# 10-M2_GPS.net
KiCad netlist of a schematic drawn in Altium Designer
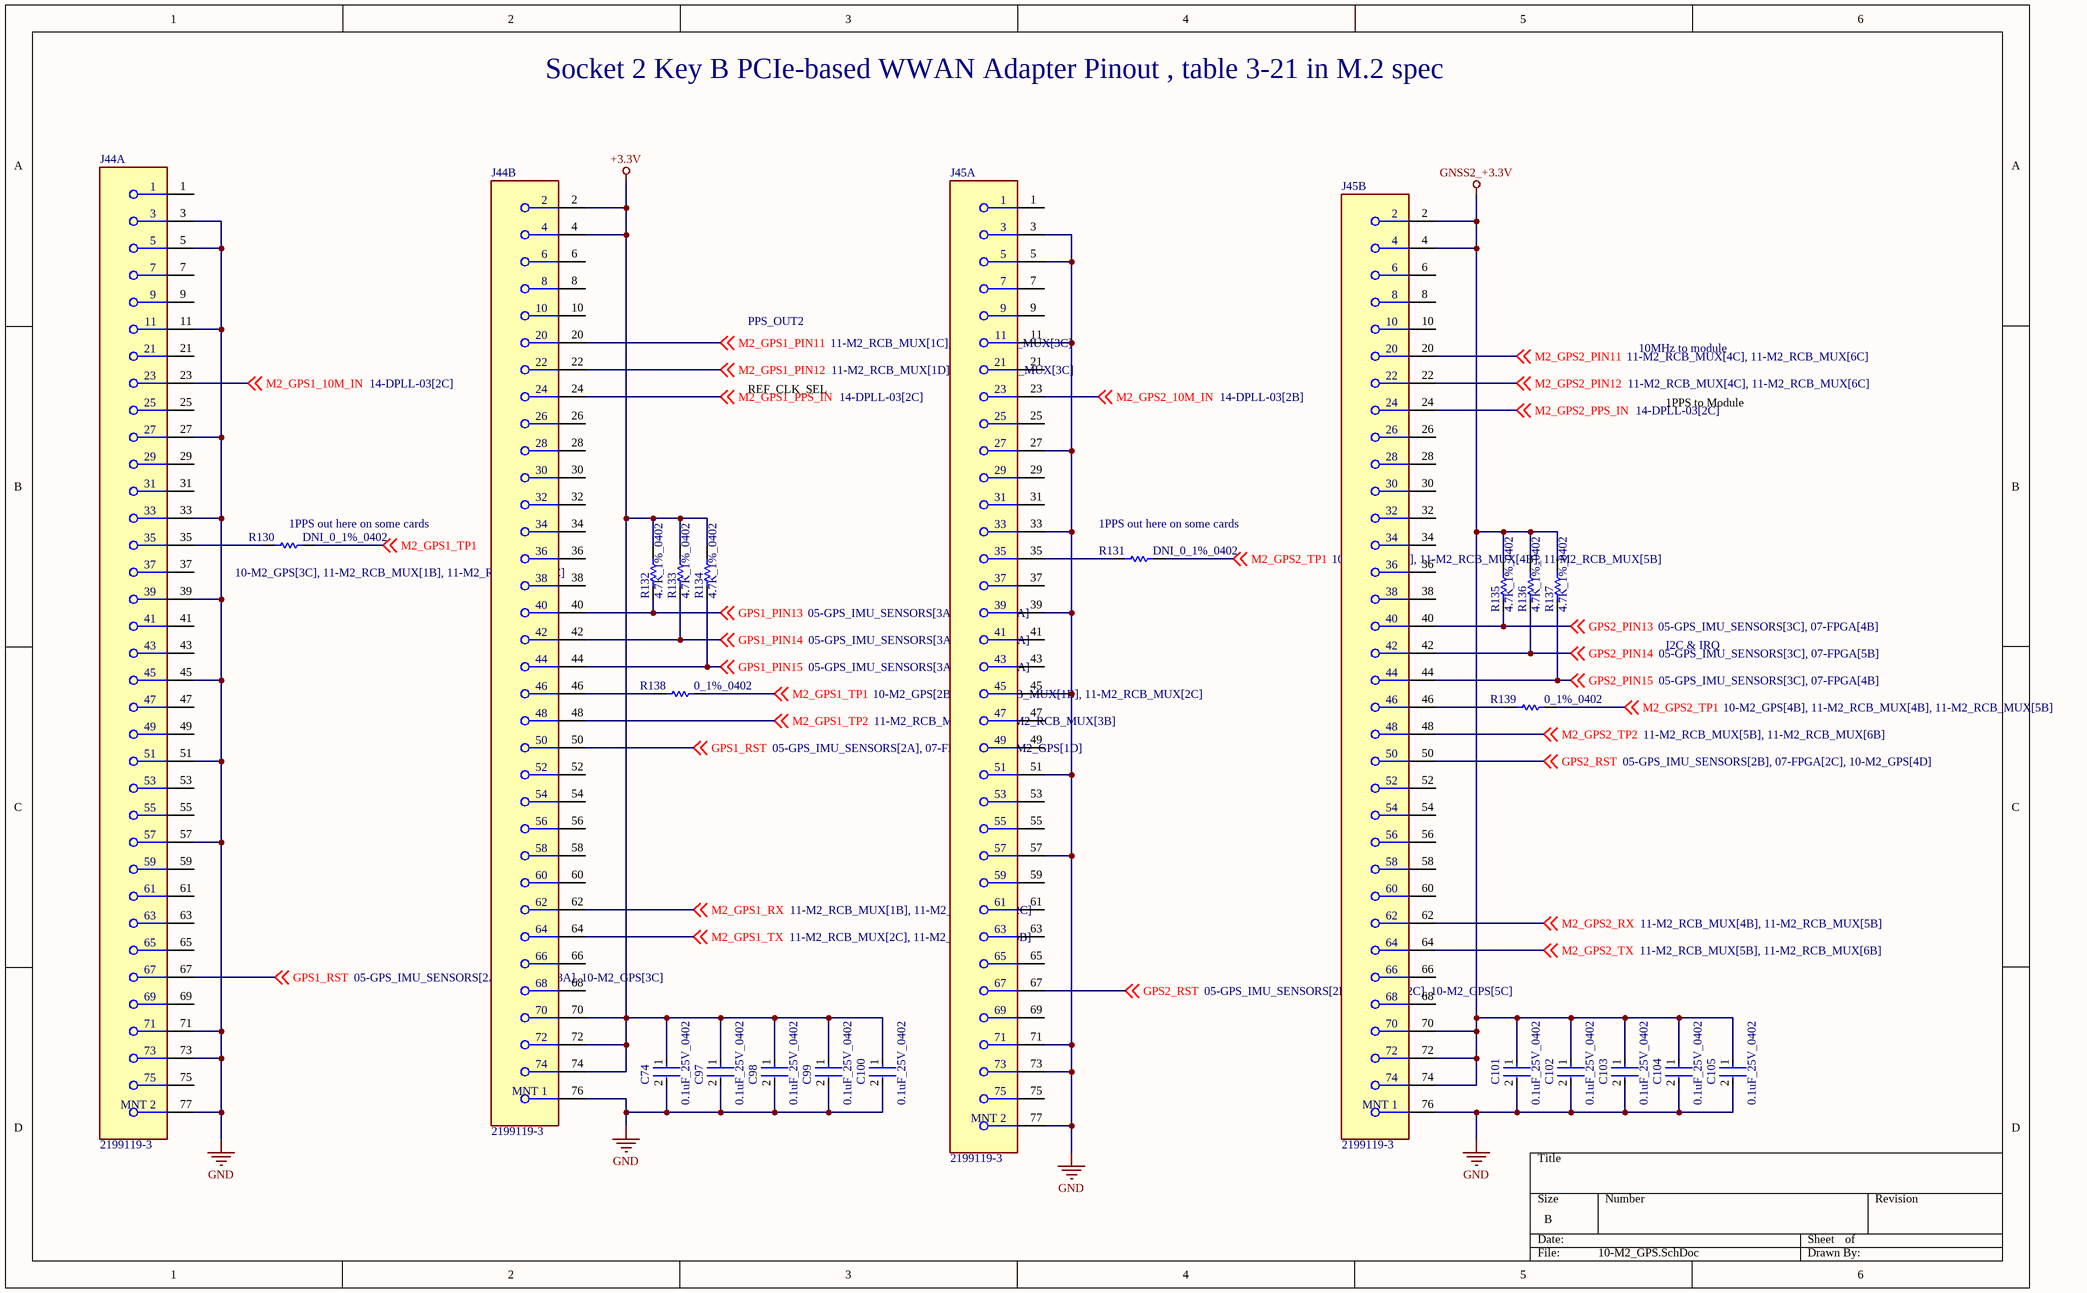
[diagram p0: 10-M2_GPS.SchDoc]

(export (version "E")
  (design (tool "Eeschema 10.0.6"))
  (components
    (comp (ref "C74")
      (value "0.1uF_25V_0402")
      (footprint "FP-0402-L_1_0_1-W_0_5_0_1-IPC_C")
      (description "General Purpose Ceramic Capacitor, 0402, 100nF, 10%, X7R, 15%, 25V")
      (fields (field (name "VOLTAGE") "25V") (field (name "TOLERANCE") "10%"))
      (libsource (lib "Altium Content Vault") (part "b4654b650e69147ec39a6b967a45e02"))
    )
    (comp (ref "C97")
      (value "0.1uF_25V_0402")
      (footprint "FP-0402-L_1_0_1-W_0_5_0_1-IPC_C")
      (description "General Purpose Ceramic Capacitor, 0402, 100nF, 10%, X7R, 15%, 25V")
      (fields (field (name "VOLTAGE") "25V") (field (name "TOLERANCE") "10%"))
      (libsource (lib "Altium Content Vault") (part "b4654b650e69147ec39a6b967a45e02"))
    )
    (comp (ref "C98")
      (value "0.1uF_25V_0402")
      (footprint "FP-0402-L_1_0_1-W_0_5_0_1-IPC_C")
      (description "General Purpose Ceramic Capacitor, 0402, 100nF, 10%, X7R, 15%, 25V")
      (fields (field (name "VOLTAGE") "25V") (field (name "TOLERANCE") "10%"))
      (libsource (lib "Altium Content Vault") (part "b4654b650e69147ec39a6b967a45e02"))
    )
    (comp (ref "C99")
      (value "0.1uF_25V_0402")
      (footprint "FP-0402-L_1_0_1-W_0_5_0_1-IPC_C")
      (description "General Purpose Ceramic Capacitor, 0402, 100nF, 10%, X7R, 15%, 25V")
      (fields (field (name "VOLTAGE") "25V") (field (name "TOLERANCE") "10%"))
      (libsource (lib "Altium Content Vault") (part "b4654b650e69147ec39a6b967a45e02"))
    )
    (comp (ref "C100")
      (value "0.1uF_25V_0402")
      (footprint "FP-0402-L_1_0_1-W_0_5_0_1-IPC_C")
      (description "General Purpose Ceramic Capacitor, 0402, 100nF, 10%, X7R, 15%, 25V")
      (fields (field (name "VOLTAGE") "25V") (field (name "TOLERANCE") "10%"))
      (libsource (lib "Altium Content Vault") (part "b4654b650e69147ec39a6b967a45e02"))
    )
    (comp (ref "C101")
      (value "0.1uF_25V_0402")
      (footprint "FP-0402-L_1_0_1-W_0_5_0_1-IPC_C")
      (description "General Purpose Ceramic Capacitor, 0402, 100nF, 10%, X7R, 15%, 25V")
      (fields (field (name "VOLTAGE") "25V") (field (name "TOLERANCE") "10%"))
      (libsource (lib "Altium Content Vault") (part "b4654b650e69147ec39a6b967a45e02"))
    )
    (comp (ref "C102")
      (value "0.1uF_25V_0402")
      (footprint "FP-0402-L_1_0_1-W_0_5_0_1-IPC_C")
      (description "General Purpose Ceramic Capacitor, 0402, 100nF, 10%, X7R, 15%, 25V")
      (fields (field (name "VOLTAGE") "25V") (field (name "TOLERANCE") "10%"))
      (libsource (lib "Altium Content Vault") (part "b4654b650e69147ec39a6b967a45e02"))
    )
    (comp (ref "C103")
      (value "0.1uF_25V_0402")
      (footprint "FP-0402-L_1_0_1-W_0_5_0_1-IPC_C")
      (description "General Purpose Ceramic Capacitor, 0402, 100nF, 10%, X7R, 15%, 25V")
      (fields (field (name "VOLTAGE") "25V") (field (name "TOLERANCE") "10%"))
      (libsource (lib "Altium Content Vault") (part "b4654b650e69147ec39a6b967a45e02"))
    )
    (comp (ref "C104")
      (value "0.1uF_25V_0402")
      (footprint "FP-0402-L_1_0_1-W_0_5_0_1-IPC_C")
      (description "General Purpose Ceramic Capacitor, 0402, 100nF, 10%, X7R, 15%, 25V")
      (fields (field (name "VOLTAGE") "25V") (field (name "TOLERANCE") "10%"))
      (libsource (lib "Altium Content Vault") (part "b4654b650e69147ec39a6b967a45e02"))
    )
    (comp (ref "C105")
      (value "0.1uF_25V_0402")
      (footprint "FP-0402-L_1_0_1-W_0_5_0_1-IPC_C")
      (description "General Purpose Ceramic Capacitor, 0402, 100nF, 10%, X7R, 15%, 25V")
      (fields (field (name "VOLTAGE") "25V") (field (name "TOLERANCE") "10%"))
      (libsource (lib "Altium Content Vault") (part "b4654b650e69147ec39a6b967a45e02"))
    )
    (comp (ref "J44")
      (value "2199119-3")
      (footprint "FP-2199119-3-MFG")
      (description "CONN M.2 FEMALE 67POS 0.020 GOLD")
      (libsource (lib "Altium Content Vault") (part "a14843ccfa78e5d0b739856168502fb"))
    )
    (comp (ref "J45")
      (value "2199119-3")
      (footprint "FP-2199119-3-MFG")
      (description "CONN M.2 FEMALE 67POS 0.020 GOLD")
      (libsource (lib "Altium Content Vault") (part "a14843ccfa78e5d0b739856168502fb"))
    )
    (comp (ref "R130")
      (value "DNI_0_1%_0402")
      (footprint "RESC1005X40X25LL05T05")
      (description "Chip Resistor, 0 Ohm, 0.1 W, -55 to 155 degC, 0402 (1005 Metric), RoHS, Tape and Reel")
      (fields (field (name "MANUFACTURER") "Panasonic") (field (name "TOLERANCE") "5%"))
      (libsource (lib "Altium Content Vault") (part "RES-2"))
    )
    (comp (ref "R131")
      (value "DNI_0_1%_0402")
      (footprint "RESC1005X40X25LL05T05")
      (description "Chip Resistor, 0 Ohm, 0.1 W, -55 to 155 degC, 0402 (1005 Metric), RoHS, Tape and Reel")
      (fields (field (name "MANUFACTURER") "Panasonic") (field (name "TOLERANCE") "5%"))
      (libsource (lib "Altium Content Vault") (part "RES-2"))
    )
    (comp (ref "R132")
      (value "4.7K_1%_0402")
      (footprint "RESC1005X40X25NL10T10")
      (fields (field (name "MANUFACTURER") "Bourns") (field (name "PART NUMBER") "CR0402-FX-4701GLF"))
      (libsource (lib "Altium Content Vault") (part "RES"))
    )
    (comp (ref "R133")
      (value "4.7K_1%_0402")
      (footprint "RESC1005X40X25NL10T10")
      (fields (field (name "MANUFACTURER") "Bourns") (field (name "PART NUMBER") "CR0402-FX-4701GLF"))
      (libsource (lib "Altium Content Vault") (part "RES"))
    )
    (comp (ref "R134")
      (value "4.7K_1%_0402")
      (footprint "RESC1005X40X25NL10T10")
      (fields (field (name "MANUFACTURER") "Bourns") (field (name "PART NUMBER") "CR0402-FX-4701GLF"))
      (libsource (lib "Altium Content Vault") (part "RES"))
    )
    (comp (ref "R135")
      (value "4.7K_1%_0402")
      (footprint "RESC1005X40X25NL10T10")
      (fields (field (name "MANUFACTURER") "Bourns") (field (name "PART NUMBER") "CR0402-FX-4701GLF"))
      (libsource (lib "Altium Content Vault") (part "RES"))
    )
    (comp (ref "R136")
      (value "4.7K_1%_0402")
      (footprint "RESC1005X40X25NL10T10")
      (fields (field (name "MANUFACTURER") "Bourns") (field (name "PART NUMBER") "CR0402-FX-4701GLF"))
      (libsource (lib "Altium Content Vault") (part "RES"))
    )
    (comp (ref "R137")
      (value "4.7K_1%_0402")
      (footprint "RESC1005X40X25NL10T10")
      (fields (field (name "MANUFACTURER") "Bourns") (field (name "PART NUMBER") "CR0402-FX-4701GLF"))
      (libsource (lib "Altium Content Vault") (part "RES"))
    )
    (comp (ref "R138")
      (value "0_1%_0402")
      (footprint "RESC1005X40X25LL05T05")
      (description "Chip Resistor, 0 Ohm, 0.1 W, -55 to 155 degC, 0402 (1005 Metric), RoHS, Tape and Reel")
      (fields (field (name "MANUFACTURER") "Panasonic") (field (name "TOLERANCE") "5%"))
      (libsource (lib "Altium Content Vault") (part "RES-2"))
    )
    (comp (ref "R139")
      (value "0_1%_0402")
      (footprint "RESC1005X40X25LL05T05")
      (description "Chip Resistor, 0 Ohm, 0.1 W, -55 to 155 degC, 0402 (1005 Metric), RoHS, Tape and Reel")
      (fields (field (name "MANUFACTURER") "Panasonic") (field (name "TOLERANCE") "5%"))
      (libsource (lib "Altium Content Vault") (part "RES-2"))
    )
  )
  (nets
    (net (code "1") (name "+3.3V") (class "Default")
      (node (ref "C100") (pin "1") (pinfunction "1_1") (pintype "passive"))
      (node (ref "C74") (pin "1") (pinfunction "1_1") (pintype "passive"))
      (node (ref "C97") (pin "1") (pinfunction "1_1") (pintype "passive"))
      (node (ref "C98") (pin "1") (pinfunction "1_1") (pintype "passive"))
      (node (ref "C99") (pin "1") (pinfunction "1_1") (pintype "passive"))
      (node (ref "J44") (pin "2") (pinfunction "2_2") (pintype "passive"))
      (node (ref "J44") (pin "4") (pinfunction "4_4") (pintype "passive"))
      (node (ref "J44") (pin "70") (pinfunction "70_70") (pintype "passive"))
      (node (ref "J44") (pin "72") (pinfunction "72_72") (pintype "passive"))
      (node (ref "J44") (pin "74") (pinfunction "74_74") (pintype "passive"))
      (node (ref "R132") (pin "2") (pinfunction "2_2") (pintype "passive"))
      (node (ref "R133") (pin "2") (pinfunction "2_2") (pintype "passive"))
      (node (ref "R134") (pin "2") (pinfunction "2_2") (pintype "passive"))
    )
    (net (code "2") (name "GND") (class "Default")
      (node (ref "C100") (pin "2") (pinfunction "2_2") (pintype "passive"))
      (node (ref "C101") (pin "2") (pinfunction "2_2") (pintype "passive"))
      (node (ref "C102") (pin "2") (pinfunction "2_2") (pintype "passive"))
      (node (ref "C103") (pin "2") (pinfunction "2_2") (pintype "passive"))
      (node (ref "C104") (pin "2") (pinfunction "2_2") (pintype "passive"))
      (node (ref "C105") (pin "2") (pinfunction "2_2") (pintype "passive"))
      (node (ref "C74") (pin "2") (pinfunction "2_2") (pintype "passive"))
      (node (ref "C97") (pin "2") (pinfunction "2_2") (pintype "passive"))
      (node (ref "C98") (pin "2") (pinfunction "2_2") (pintype "passive"))
      (node (ref "C99") (pin "2") (pinfunction "2_2") (pintype "passive"))
      (node (ref "J44") (pin "11") (pinfunction "11_11") (pintype "passive"))
      (node (ref "J44") (pin "27") (pinfunction "27_27") (pintype "passive"))
      (node (ref "J44") (pin "3") (pinfunction "3_3") (pintype "passive"))
      (node (ref "J44") (pin "33") (pinfunction "33_33") (pintype "passive"))
      (node (ref "J44") (pin "39") (pinfunction "39_39") (pintype "passive"))
      (node (ref "J44") (pin "45") (pinfunction "45_45") (pintype "passive"))
      (node (ref "J44") (pin "5") (pinfunction "5_5") (pintype "passive"))
      (node (ref "J44") (pin "51") (pinfunction "51_51") (pintype "passive"))
      (node (ref "J44") (pin "57") (pinfunction "57_57") (pintype "passive"))
      (node (ref "J44") (pin "71") (pinfunction "71_71") (pintype "passive"))
      (node (ref "J44") (pin "73") (pinfunction "73_73") (pintype "passive"))
      (node (ref "J44") (pin "76") (pinfunction "MNT_1_76") (pintype "passive"))
      (node (ref "J44") (pin "77") (pinfunction "MNT_2_77") (pintype "passive"))
      (node (ref "J45") (pin "11") (pinfunction "11_11") (pintype "passive"))
      (node (ref "J45") (pin "27") (pinfunction "27_27") (pintype "passive"))
      (node (ref "J45") (pin "3") (pinfunction "3_3") (pintype "passive"))
      (node (ref "J45") (pin "33") (pinfunction "33_33") (pintype "passive"))
      (node (ref "J45") (pin "39") (pinfunction "39_39") (pintype "passive"))
      (node (ref "J45") (pin "45") (pinfunction "45_45") (pintype "passive"))
      (node (ref "J45") (pin "5") (pinfunction "5_5") (pintype "passive"))
      (node (ref "J45") (pin "51") (pinfunction "51_51") (pintype "passive"))
      (node (ref "J45") (pin "57") (pinfunction "57_57") (pintype "passive"))
      (node (ref "J45") (pin "71") (pinfunction "71_71") (pintype "passive"))
      (node (ref "J45") (pin "73") (pinfunction "73_73") (pintype "passive"))
      (node (ref "J45") (pin "76") (pinfunction "MNT_1_76") (pintype "passive"))
      (node (ref "J45") (pin "77") (pinfunction "MNT_2_77") (pintype "passive"))
    )
    (net (code "3") (name "GNSS2_+3.3V") (class "Default")
      (node (ref "C101") (pin "1") (pinfunction "1_1") (pintype "passive"))
      (node (ref "C102") (pin "1") (pinfunction "1_1") (pintype "passive"))
      (node (ref "C103") (pin "1") (pinfunction "1_1") (pintype "passive"))
      (node (ref "C104") (pin "1") (pinfunction "1_1") (pintype "passive"))
      (node (ref "C105") (pin "1") (pinfunction "1_1") (pintype "passive"))
      (node (ref "J45") (pin "2") (pinfunction "2_2") (pintype "passive"))
      (node (ref "J45") (pin "4") (pinfunction "4_4") (pintype "passive"))
      (node (ref "J45") (pin "70") (pinfunction "70_70") (pintype "passive"))
      (node (ref "J45") (pin "72") (pinfunction "72_72") (pintype "passive"))
      (node (ref "J45") (pin "74") (pinfunction "74_74") (pintype "passive"))
      (node (ref "R135") (pin "2") (pinfunction "2_2") (pintype "passive"))
      (node (ref "R136") (pin "2") (pinfunction "2_2") (pintype "passive"))
      (node (ref "R137") (pin "2") (pinfunction "2_2") (pintype "passive"))
    )
    (net (code "4") (name "GPS1_PIN13") (class "Default")
      (node (ref "J44") (pin "40") (pinfunction "40_40") (pintype "passive"))
      (node (ref "R132") (pin "1") (pinfunction "1_1") (pintype "passive"))
    )
    (net (code "5") (name "GPS1_PIN14") (class "Default")
      (node (ref "J44") (pin "42") (pinfunction "42_42") (pintype "passive"))
      (node (ref "R133") (pin "1") (pinfunction "1_1") (pintype "passive"))
    )
    (net (code "6") (name "GPS1_PIN15") (class "Default")
      (node (ref "J44") (pin "44") (pinfunction "44_44") (pintype "passive"))
      (node (ref "R134") (pin "1") (pinfunction "1_1") (pintype "passive"))
    )
    (net (code "7") (name "GPS1_RST") (class "Default")
      (node (ref "J44") (pin "50") (pinfunction "50_50") (pintype "passive"))
      (node (ref "J44") (pin "67") (pinfunction "67_67") (pintype "passive"))
    )
    (net (code "8") (name "GPS2_PIN13") (class "Default")
      (node (ref "J45") (pin "40") (pinfunction "40_40") (pintype "passive"))
      (node (ref "R135") (pin "1") (pinfunction "1_1") (pintype "passive"))
    )
    (net (code "9") (name "GPS2_PIN14") (class "Default")
      (node (ref "J45") (pin "42") (pinfunction "42_42") (pintype "passive"))
      (node (ref "R136") (pin "1") (pinfunction "1_1") (pintype "passive"))
    )
    (net (code "10") (name "GPS2_PIN15") (class "Default")
      (node (ref "J45") (pin "44") (pinfunction "44_44") (pintype "passive"))
      (node (ref "R137") (pin "1") (pinfunction "1_1") (pintype "passive"))
    )
    (net (code "11") (name "GPS2_RST") (class "Default")
      (node (ref "J45") (pin "50") (pinfunction "50_50") (pintype "passive"))
      (node (ref "J45") (pin "67") (pinfunction "67_67") (pintype "passive"))
    )
    (net (code "12") (name "M2_GPS1_10M_IN") (class "Default")
      (node (ref "J44") (pin "23") (pinfunction "23_23") (pintype "passive"))
    )
    (net (code "13") (name "M2_GPS1_PIN11") (class "Default")
      (node (ref "J44") (pin "20") (pinfunction "20_20") (pintype "passive"))
    )
    (net (code "14") (name "M2_GPS1_PIN12") (class "Default")
      (node (ref "J44") (pin "22") (pinfunction "22_22") (pintype "passive"))
    )
    (net (code "15") (name "M2_GPS1_PPS_IN") (class "Default")
      (node (ref "J44") (pin "24") (pinfunction "24_24") (pintype "passive"))
    )
    (net (code "16") (name "M2_GPS1_RX") (class "Default")
      (node (ref "J44") (pin "62") (pinfunction "62_62") (pintype "passive"))
    )
    (net (code "17") (name "M2_GPS1_TP1") (class "Default")
      (node (ref "R130") (pin "2") (pinfunction "2_2") (pintype "passive"))
      (node (ref "R138") (pin "2") (pinfunction "2_2") (pintype "passive"))
    )
    (net (code "18") (name "M2_GPS1_TP2") (class "Default")
      (node (ref "J44") (pin "48") (pinfunction "48_48") (pintype "passive"))
    )
    (net (code "19") (name "M2_GPS1_TX") (class "Default")
      (node (ref "J44") (pin "64") (pinfunction "64_64") (pintype "passive"))
    )
    (net (code "20") (name "M2_GPS2_10M_IN") (class "Default")
      (node (ref "J45") (pin "23") (pinfunction "23_23") (pintype "passive"))
    )
    (net (code "21") (name "M2_GPS2_PIN11") (class "Default")
      (node (ref "J45") (pin "20") (pinfunction "20_20") (pintype "passive"))
    )
    (net (code "22") (name "M2_GPS2_PIN12") (class "Default")
      (node (ref "J45") (pin "22") (pinfunction "22_22") (pintype "passive"))
    )
    (net (code "23") (name "M2_GPS2_PPS_IN") (class "Default")
      (node (ref "J45") (pin "24") (pinfunction "24_24") (pintype "passive"))
    )
    (net (code "24") (name "M2_GPS2_RX") (class "Default")
      (node (ref "J45") (pin "62") (pinfunction "62_62") (pintype "passive"))
    )
    (net (code "25") (name "M2_GPS2_TP1") (class "Default")
      (node (ref "R131") (pin "2") (pinfunction "2_2") (pintype "passive"))
      (node (ref "R139") (pin "2") (pinfunction "2_2") (pintype "passive"))
    )
    (net (code "26") (name "M2_GPS2_TP2") (class "Default")
      (node (ref "J45") (pin "48") (pinfunction "48_48") (pintype "passive"))
    )
    (net (code "27") (name "M2_GPS2_TX") (class "Default")
      (node (ref "J45") (pin "64") (pinfunction "64_64") (pintype "passive"))
    )
    (net (code "28") (name "Net-(J44-Pad35)") (class "Default")
      (node (ref "J44") (pin "35") (pinfunction "35_35") (pintype "passive"))
      (node (ref "R130") (pin "1") (pinfunction "1_1") (pintype "passive"))
    )
    (net (code "29") (name "Net-(J44-Pad46)") (class "Default")
      (node (ref "J44") (pin "46") (pinfunction "46_46") (pintype "passive"))
      (node (ref "R138") (pin "1") (pinfunction "1_1") (pintype "passive"))
    )
    (net (code "30") (name "Net-(J45-Pad35)") (class "Default")
      (node (ref "J45") (pin "35") (pinfunction "35_35") (pintype "passive"))
      (node (ref "R131") (pin "1") (pinfunction "1_1") (pintype "passive"))
    )
    (net (code "31") (name "Net-(J45-Pad46)") (class "Default")
      (node (ref "J45") (pin "46") (pinfunction "46_46") (pintype "passive"))
      (node (ref "R139") (pin "1") (pinfunction "1_1") (pintype "passive"))
    )
    (net (code "32") (name "unconnected-(J44-Pad1)") (class "Default")
      (node (ref "J44") (pin "1") (pinfunction "1_1") (pintype "passive"))
    )
    (net (code "33") (name "unconnected-(J44-Pad6)") (class "Default")
      (node (ref "J44") (pin "6") (pinfunction "6_6") (pintype "passive"))
    )
    (net (code "34") (name "unconnected-(J44-Pad7)") (class "Default")
      (node (ref "J44") (pin "7") (pinfunction "7_7") (pintype "passive"))
    )
    (net (code "35") (name "unconnected-(J44-Pad8)") (class "Default")
      (node (ref "J44") (pin "8") (pinfunction "8_8") (pintype "passive"))
    )
    (net (code "36") (name "unconnected-(J44-Pad9)") (class "Default")
      (node (ref "J44") (pin "9") (pinfunction "9_9") (pintype "passive"))
    )
    (net (code "37") (name "unconnected-(J44-Pad10)") (class "Default")
      (node (ref "J44") (pin "10") (pinfunction "10_10") (pintype "passive"))
    )
    (net (code "38") (name "unconnected-(J44-Pad21)") (class "Default")
      (node (ref "J44") (pin "21") (pinfunction "21_21") (pintype "passive"))
    )
    (net (code "39") (name "unconnected-(J44-Pad25)") (class "Default")
      (node (ref "J44") (pin "25") (pinfunction "25_25") (pintype "passive"))
    )
    (net (code "40") (name "unconnected-(J44-Pad26)") (class "Default")
      (node (ref "J44") (pin "26") (pinfunction "26_26") (pintype "passive"))
    )
    (net (code "41") (name "unconnected-(J44-Pad28)") (class "Default")
      (node (ref "J44") (pin "28") (pinfunction "28_28") (pintype "passive"))
    )
    (net (code "42") (name "unconnected-(J44-Pad29)") (class "Default")
      (node (ref "J44") (pin "29") (pinfunction "29_29") (pintype "passive"))
    )
    (net (code "43") (name "unconnected-(J44-Pad30)") (class "Default")
      (node (ref "J44") (pin "30") (pinfunction "30_30") (pintype "passive"))
    )
    (net (code "44") (name "unconnected-(J44-Pad31)") (class "Default")
      (node (ref "J44") (pin "31") (pinfunction "31_31") (pintype "passive"))
    )
    (net (code "45") (name "unconnected-(J44-Pad32)") (class "Default")
      (node (ref "J44") (pin "32") (pinfunction "32_32") (pintype "passive"))
    )
    (net (code "46") (name "unconnected-(J44-Pad34)") (class "Default")
      (node (ref "J44") (pin "34") (pinfunction "34_34") (pintype "passive"))
    )
    (net (code "47") (name "unconnected-(J44-Pad36)") (class "Default")
      (node (ref "J44") (pin "36") (pinfunction "36_36") (pintype "passive"))
    )
    (net (code "48") (name "unconnected-(J44-Pad37)") (class "Default")
      (node (ref "J44") (pin "37") (pinfunction "37_37") (pintype "passive"))
    )
    (net (code "49") (name "unconnected-(J44-Pad38)") (class "Default")
      (node (ref "J44") (pin "38") (pinfunction "38_38") (pintype "passive"))
    )
    (net (code "50") (name "unconnected-(J44-Pad41)") (class "Default")
      (node (ref "J44") (pin "41") (pinfunction "41_41") (pintype "passive"))
    )
    (net (code "51") (name "unconnected-(J44-Pad43)") (class "Default")
      (node (ref "J44") (pin "43") (pinfunction "43_43") (pintype "passive"))
    )
    (net (code "52") (name "unconnected-(J44-Pad47)") (class "Default")
      (node (ref "J44") (pin "47") (pinfunction "47_47") (pintype "passive"))
    )
    (net (code "53") (name "unconnected-(J44-Pad49)") (class "Default")
      (node (ref "J44") (pin "49") (pinfunction "49_49") (pintype "passive"))
    )
    (net (code "54") (name "unconnected-(J44-Pad52)") (class "Default")
      (node (ref "J44") (pin "52") (pinfunction "52_52") (pintype "passive"))
    )
    (net (code "55") (name "unconnected-(J44-Pad53)") (class "Default")
      (node (ref "J44") (pin "53") (pinfunction "53_53") (pintype "passive"))
    )
    (net (code "56") (name "unconnected-(J44-Pad54)") (class "Default")
      (node (ref "J44") (pin "54") (pinfunction "54_54") (pintype "passive"))
    )
    (net (code "57") (name "unconnected-(J44-Pad55)") (class "Default")
      (node (ref "J44") (pin "55") (pinfunction "55_55") (pintype "passive"))
    )
    (net (code "58") (name "unconnected-(J44-Pad56)") (class "Default")
      (node (ref "J44") (pin "56") (pinfunction "56_56") (pintype "passive"))
    )
    (net (code "59") (name "unconnected-(J44-Pad58)") (class "Default")
      (node (ref "J44") (pin "58") (pinfunction "58_58") (pintype "passive"))
    )
    (net (code "60") (name "unconnected-(J44-Pad59)") (class "Default")
      (node (ref "J44") (pin "59") (pinfunction "59_59") (pintype "passive"))
    )
    (net (code "61") (name "unconnected-(J44-Pad60)") (class "Default")
      (node (ref "J44") (pin "60") (pinfunction "60_60") (pintype "passive"))
    )
    (net (code "62") (name "unconnected-(J44-Pad61)") (class "Default")
      (node (ref "J44") (pin "61") (pinfunction "61_61") (pintype "passive"))
    )
    (net (code "63") (name "unconnected-(J44-Pad63)") (class "Default")
      (node (ref "J44") (pin "63") (pinfunction "63_63") (pintype "passive"))
    )
    (net (code "64") (name "unconnected-(J44-Pad65)") (class "Default")
      (node (ref "J44") (pin "65") (pinfunction "65_65") (pintype "passive"))
    )
    (net (code "65") (name "unconnected-(J44-Pad66)") (class "Default")
      (node (ref "J44") (pin "66") (pinfunction "66_66") (pintype "passive"))
    )
    (net (code "66") (name "unconnected-(J44-Pad68)") (class "Default")
      (node (ref "J44") (pin "68") (pinfunction "68_68") (pintype "passive"))
    )
    (net (code "67") (name "unconnected-(J44-Pad69)") (class "Default")
      (node (ref "J44") (pin "69") (pinfunction "69_69") (pintype "passive"))
    )
    (net (code "68") (name "unconnected-(J44-Pad75)") (class "Default")
      (node (ref "J44") (pin "75") (pinfunction "75_75") (pintype "passive"))
    )
    (net (code "69") (name "unconnected-(J45-Pad1)") (class "Default")
      (node (ref "J45") (pin "1") (pinfunction "1_1") (pintype "passive"))
    )
    (net (code "70") (name "unconnected-(J45-Pad6)") (class "Default")
      (node (ref "J45") (pin "6") (pinfunction "6_6") (pintype "passive"))
    )
    (net (code "71") (name "unconnected-(J45-Pad7)") (class "Default")
      (node (ref "J45") (pin "7") (pinfunction "7_7") (pintype "passive"))
    )
    (net (code "72") (name "unconnected-(J45-Pad8)") (class "Default")
      (node (ref "J45") (pin "8") (pinfunction "8_8") (pintype "passive"))
    )
    (net (code "73") (name "unconnected-(J45-Pad9)") (class "Default")
      (node (ref "J45") (pin "9") (pinfunction "9_9") (pintype "passive"))
    )
    (net (code "74") (name "unconnected-(J45-Pad10)") (class "Default")
      (node (ref "J45") (pin "10") (pinfunction "10_10") (pintype "passive"))
    )
    (net (code "75") (name "unconnected-(J45-Pad21)") (class "Default")
      (node (ref "J45") (pin "21") (pinfunction "21_21") (pintype "passive"))
    )
    (net (code "76") (name "unconnected-(J45-Pad25)") (class "Default")
      (node (ref "J45") (pin "25") (pinfunction "25_25") (pintype "passive"))
    )
    (net (code "77") (name "unconnected-(J45-Pad26)") (class "Default")
      (node (ref "J45") (pin "26") (pinfunction "26_26") (pintype "passive"))
    )
    (net (code "78") (name "unconnected-(J45-Pad28)") (class "Default")
      (node (ref "J45") (pin "28") (pinfunction "28_28") (pintype "passive"))
    )
    (net (code "79") (name "unconnected-(J45-Pad29)") (class "Default")
      (node (ref "J45") (pin "29") (pinfunction "29_29") (pintype "passive"))
    )
    (net (code "80") (name "unconnected-(J45-Pad30)") (class "Default")
      (node (ref "J45") (pin "30") (pinfunction "30_30") (pintype "passive"))
    )
    (net (code "81") (name "unconnected-(J45-Pad31)") (class "Default")
      (node (ref "J45") (pin "31") (pinfunction "31_31") (pintype "passive"))
    )
    (net (code "82") (name "unconnected-(J45-Pad32)") (class "Default")
      (node (ref "J45") (pin "32") (pinfunction "32_32") (pintype "passive"))
    )
    (net (code "83") (name "unconnected-(J45-Pad34)") (class "Default")
      (node (ref "J45") (pin "34") (pinfunction "34_34") (pintype "passive"))
    )
    (net (code "84") (name "unconnected-(J45-Pad36)") (class "Default")
      (node (ref "J45") (pin "36") (pinfunction "36_36") (pintype "passive"))
    )
    (net (code "85") (name "unconnected-(J45-Pad37)") (class "Default")
      (node (ref "J45") (pin "37") (pinfunction "37_37") (pintype "passive"))
    )
    (net (code "86") (name "unconnected-(J45-Pad38)") (class "Default")
      (node (ref "J45") (pin "38") (pinfunction "38_38") (pintype "passive"))
    )
    (net (code "87") (name "unconnected-(J45-Pad41)") (class "Default")
      (node (ref "J45") (pin "41") (pinfunction "41_41") (pintype "passive"))
    )
    (net (code "88") (name "unconnected-(J45-Pad43)") (class "Default")
      (node (ref "J45") (pin "43") (pinfunction "43_43") (pintype "passive"))
    )
    (net (code "89") (name "unconnected-(J45-Pad47)") (class "Default")
      (node (ref "J45") (pin "47") (pinfunction "47_47") (pintype "passive"))
    )
    (net (code "90") (name "unconnected-(J45-Pad49)") (class "Default")
      (node (ref "J45") (pin "49") (pinfunction "49_49") (pintype "passive"))
    )
    (net (code "91") (name "unconnected-(J45-Pad52)") (class "Default")
      (node (ref "J45") (pin "52") (pinfunction "52_52") (pintype "passive"))
    )
    (net (code "92") (name "unconnected-(J45-Pad53)") (class "Default")
      (node (ref "J45") (pin "53") (pinfunction "53_53") (pintype "passive"))
    )
    (net (code "93") (name "unconnected-(J45-Pad54)") (class "Default")
      (node (ref "J45") (pin "54") (pinfunction "54_54") (pintype "passive"))
    )
    (net (code "94") (name "unconnected-(J45-Pad55)") (class "Default")
      (node (ref "J45") (pin "55") (pinfunction "55_55") (pintype "passive"))
    )
    (net (code "95") (name "unconnected-(J45-Pad56)") (class "Default")
      (node (ref "J45") (pin "56") (pinfunction "56_56") (pintype "passive"))
    )
    (net (code "96") (name "unconnected-(J45-Pad58)") (class "Default")
      (node (ref "J45") (pin "58") (pinfunction "58_58") (pintype "passive"))
    )
    (net (code "97") (name "unconnected-(J45-Pad59)") (class "Default")
      (node (ref "J45") (pin "59") (pinfunction "59_59") (pintype "passive"))
    )
    (net (code "98") (name "unconnected-(J45-Pad60)") (class "Default")
      (node (ref "J45") (pin "60") (pinfunction "60_60") (pintype "passive"))
    )
    (net (code "99") (name "unconnected-(J45-Pad61)") (class "Default")
      (node (ref "J45") (pin "61") (pinfunction "61_61") (pintype "passive"))
    )
    (net (code "100") (name "unconnected-(J45-Pad63)") (class "Default")
      (node (ref "J45") (pin "63") (pinfunction "63_63") (pintype "passive"))
    )
    (net (code "101") (name "unconnected-(J45-Pad65)") (class "Default")
      (node (ref "J45") (pin "65") (pinfunction "65_65") (pintype "passive"))
    )
    (net (code "102") (name "unconnected-(J45-Pad66)") (class "Default")
      (node (ref "J45") (pin "66") (pinfunction "66_66") (pintype "passive"))
    )
    (net (code "103") (name "unconnected-(J45-Pad68)") (class "Default")
      (node (ref "J45") (pin "68") (pinfunction "68_68") (pintype "passive"))
    )
    (net (code "104") (name "unconnected-(J45-Pad69)") (class "Default")
      (node (ref "J45") (pin "69") (pinfunction "69_69") (pintype "passive"))
    )
    (net (code "105") (name "unconnected-(J45-Pad75)") (class "Default")
      (node (ref "J45") (pin "75") (pinfunction "75_75") (pintype "passive"))
    )
  )
)
